# Wifi_RGB_v1.net
KiCad netlist of a schematic drawn in Altium Designer
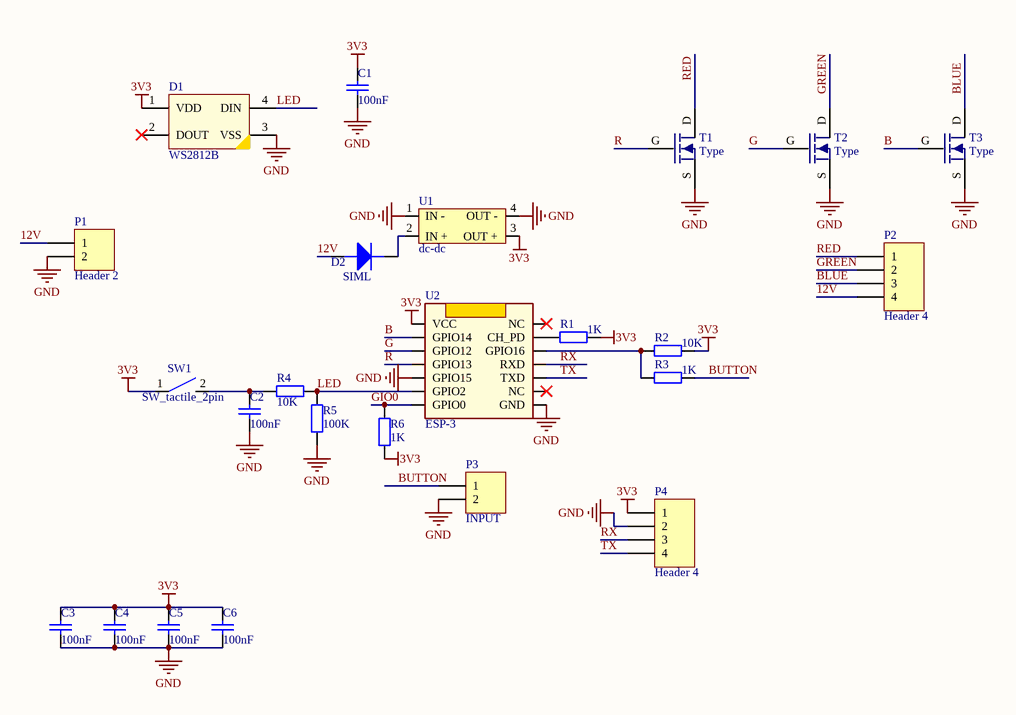
[diagram p0: Wifi_RGB_v1.SchDoc]

(export (version "E")
  (design (tool "Eeschema 10.0.6"))
  (components
    (comp (ref "C1")
      (value "100nF")
      (footprint "FP_0603_CAP_080")
      (description "Capacitor")
      (libsource (lib "Miscellaneous Devices") (part "Cap"))
    )
    (comp (ref "C2")
      (value "100nF")
      (footprint "FP_0603_CAP_080")
      (description "Capacitor")
      (libsource (lib "Miscellaneous Devices") (part "Cap"))
    )
    (comp (ref "C3")
      (value "100nF")
      (footprint "FP_0603_CAP_080")
      (description "Capacitor")
      (libsource (lib "Miscellaneous Devices") (part "Cap"))
    )
    (comp (ref "C4")
      (value "100nF")
      (footprint "FP_0603_CAP_080")
      (description "Capacitor")
      (libsource (lib "Miscellaneous Devices") (part "Cap"))
    )
    (comp (ref "C5")
      (value "100nF")
      (footprint "FP_0603_CAP_080")
      (description "Capacitor")
      (libsource (lib "Miscellaneous Devices") (part "Cap"))
    )
    (comp (ref "C6")
      (value "100nF")
      (footprint "FP_0603_CAP_080")
      (description "Capacitor")
      (libsource (lib "Miscellaneous Devices") (part "Cap"))
    )
    (comp (ref "D1")
      (value "WS2812B")
      (footprint "LED_5050_4pin")
      (libsource (lib "Led_optical") (part "WS2812B"))
    )
    (comp (ref "D2") (value "SIML") (footprint "subsma") (libsource (lib "Diode") (part "DIODE_big")))
    (comp (ref "P1")
      (value "Header 2")
      (footprint "Sorkapocs 2P 5mm")
      (description "Header, 2-Pin")
      (fields (field (name "PUBLISHER") "Altium Limited"))
      (libsource (lib "Miscellaneous Connectors") (part "Header 2"))
    )
    (comp (ref "P2")
      (value "Header 4")
      (footprint "Sorkapocs 4P 5mm")
      (description "Header, 4-Pin")
      (fields (field (name "PUBLISHER") "Altium Limited"))
      (libsource (lib "Miscellaneous Connectors") (part "Header 4"))
    )
    (comp (ref "P3")
      (value "INPUT")
      (footprint "HDR1X2")
      (description "Header, 2-Pin")
      (fields (field (name "PUBLISHER") "Altium Limited"))
      (libsource (lib "Miscellaneous Connectors") (part "Header 2"))
    )
    (comp (ref "P4")
      (value "Header 4")
      (footprint "HDR1X4")
      (description "Header, 4-Pin")
      (fields (field (name "PUBLISHER") "Altium Limited"))
      (libsource (lib "Miscellaneous Connectors") (part "Header 4"))
    )
    (comp (ref "R1")
      (value "1K")
      (footprint "FP_0603_RES")
      (description "Resistor")
      (libsource (lib "Miscellaneous Devices") (part "Res3"))
    )
    (comp (ref "R2")
      (value "10K")
      (footprint "FP_0603_RES")
      (description "Resistor")
      (libsource (lib "Miscellaneous Devices") (part "Res3"))
    )
    (comp (ref "R3")
      (value "1K")
      (footprint "FP_0603_RES")
      (description "Resistor")
      (libsource (lib "Miscellaneous Devices") (part "Res3"))
    )
    (comp (ref "R4")
      (value "10K")
      (footprint "FP_0603_RES")
      (description "Resistor")
      (libsource (lib "") (part "Res3_1"))
    )
    (comp (ref "R5")
      (value "100K")
      (footprint "FP_0603_RES")
      (description "Resistor")
      (libsource (lib "") (part "Res3_2"))
    )
    (comp (ref "R6")
      (value "1K")
      (footprint "FP_0603_RES")
      (description "Resistor")
      (libsource (lib "") (part "Res3_2"))
    )
    (comp (ref "SW1")
      (value "SW_tactile_2pin")
      (footprint "SW_TACT_2PIN")
      (libsource (lib "Switch") (part "SW_tactile_2pin"))
    )
    (comp (ref "T1") (value "Type") (footprint "FET_SOT23") (libsource (lib "FET") (part "NMOS")))
    (comp (ref "T2") (value "Type") (footprint "FET_SOT23") (libsource (lib "FET") (part "NMOS")))
    (comp (ref "T3") (value "Type") (footprint "FET_SOT23") (libsource (lib "FET") (part "NMOS")))
    (comp (ref "U1")
      (value "dc-dc")
      (footprint "DC-DC modul")
      (description "Step down dc-dc module")
      (libsource (lib "Modul") (part "DC-DC modul"))
    )
    (comp (ref "U2")
      (value "ESP-3")
      (footprint "ESP_3")
      (description "ESP-3wifi module")
      (libsource (lib "Modul") (part "ESP-3"))
    )
  )
  (nets
    (net (code "1") (name "/12V") (class "Default")
      (node (ref "D2") (pin "A") (pinfunction "A_A") (pintype "passive"))
      (node (ref "P1") (pin "1") (pinfunction "1_1") (pintype "passive"))
      (node (ref "P2") (pin "4") (pinfunction "4_4") (pintype "passive"))
    )
    (net (code "2") (name "/B") (class "Default")
      (node (ref "T3") (pin "G") (pinfunction "G_G") (pintype "passive"))
      (node (ref "U2") (pin "2") (pinfunction "GPIO14_2") (pintype "passive"))
    )
    (net (code "3") (name "/BLUE") (class "Default")
      (node (ref "P2") (pin "3") (pinfunction "3_3") (pintype "passive"))
      (node (ref "T3") (pin "D") (pinfunction "D_D") (pintype "passive"))
    )
    (net (code "4") (name "/BUTTON") (class "Default")
      (node (ref "P3") (pin "1") (pinfunction "1_1") (pintype "passive"))
      (node (ref "R3") (pin "1") (pinfunction "1_1") (pintype "passive"))
    )
    (net (code "5") (name "/G") (class "Default")
      (node (ref "T2") (pin "G") (pinfunction "G_G") (pintype "passive"))
      (node (ref "U2") (pin "3") (pinfunction "GPIO12_3") (pintype "passive"))
    )
    (net (code "6") (name "/GIO0") (class "Default")
      (node (ref "R6") (pin "1") (pinfunction "1_1") (pintype "passive"))
      (node (ref "U2") (pin "7") (pinfunction "GPIO0_7") (pintype "passive"))
    )
    (net (code "7") (name "/GREEN") (class "Default")
      (node (ref "P2") (pin "2") (pinfunction "2_2") (pintype "passive"))
      (node (ref "T2") (pin "D") (pinfunction "D_D") (pintype "passive"))
    )
    (net (code "8") (name "/LED") (class "Default")
      (node (ref "D1") (pin "4") (pinfunction "DIN_4") (pintype "passive"))
      (node (ref "R4") (pin "2") (pinfunction "2_2") (pintype "passive"))
      (node (ref "R5") (pin "1") (pinfunction "1_1") (pintype "passive"))
      (node (ref "U2") (pin "6") (pinfunction "GPIO2_6") (pintype "passive"))
    )
    (net (code "9") (name "/R") (class "Default")
      (node (ref "T1") (pin "G") (pinfunction "G_G") (pintype "passive"))
      (node (ref "U2") (pin "4") (pinfunction "GPIO13_4") (pintype "passive"))
    )
    (net (code "10") (name "/RED") (class "Default")
      (node (ref "P2") (pin "1") (pinfunction "1_1") (pintype "passive"))
      (node (ref "T1") (pin "D") (pinfunction "D_D") (pintype "passive"))
    )
    (net (code "11") (name "/RX") (class "Default")
      (node (ref "P4") (pin "3") (pinfunction "3_3") (pintype "passive"))
      (node (ref "U2") (pin "11") (pinfunction "RXD_11") (pintype "passive"))
    )
    (net (code "12") (name "/TX") (class "Default")
      (node (ref "P4") (pin "4") (pinfunction "4_4") (pintype "passive"))
      (node (ref "U2") (pin "10") (pinfunction "TXD_10") (pintype "passive"))
    )
    (net (code "13") (name "3V3") (class "Default")
      (node (ref "C1") (pin "1") (pinfunction "1_1") (pintype "passive"))
      (node (ref "C3") (pin "1") (pinfunction "1_1") (pintype "passive"))
      (node (ref "C4") (pin "1") (pinfunction "1_1") (pintype "passive"))
      (node (ref "C5") (pin "1") (pinfunction "1_1") (pintype "passive"))
      (node (ref "C6") (pin "1") (pinfunction "1_1") (pintype "passive"))
      (node (ref "D1") (pin "1") (pinfunction "VDD_1") (pintype "passive"))
      (node (ref "P4") (pin "1") (pinfunction "1_1") (pintype "passive"))
      (node (ref "R1") (pin "1") (pinfunction "1_1") (pintype "passive"))
      (node (ref "R2") (pin "1") (pinfunction "1_1") (pintype "passive"))
      (node (ref "R6") (pin "2") (pinfunction "2_2") (pintype "passive"))
      (node (ref "SW1") (pin "1") (pinfunction "1_1") (pintype "passive"))
      (node (ref "U1") (pin "3") (pinfunction "OUT_+_3") (pintype "passive"))
      (node (ref "U2") (pin "1") (pinfunction "VCC_1") (pintype "passive"))
    )
    (net (code "14") (name "GND") (class "Default")
      (node (ref "C1") (pin "2") (pinfunction "2_2") (pintype "passive"))
      (node (ref "C2") (pin "2") (pinfunction "2_2") (pintype "passive"))
      (node (ref "C3") (pin "2") (pinfunction "2_2") (pintype "passive"))
      (node (ref "C4") (pin "2") (pinfunction "2_2") (pintype "passive"))
      (node (ref "C5") (pin "2") (pinfunction "2_2") (pintype "passive"))
      (node (ref "C6") (pin "2") (pinfunction "2_2") (pintype "passive"))
      (node (ref "D1") (pin "3") (pinfunction "VSS_3") (pintype "passive"))
      (node (ref "P1") (pin "2") (pinfunction "2_2") (pintype "passive"))
      (node (ref "P3") (pin "2") (pinfunction "2_2") (pintype "passive"))
      (node (ref "P4") (pin "2") (pinfunction "2_2") (pintype "passive"))
      (node (ref "R5") (pin "2") (pinfunction "2_2") (pintype "passive"))
      (node (ref "T1") (pin "S") (pinfunction "S_S") (pintype "passive"))
      (node (ref "T2") (pin "S") (pinfunction "S_S") (pintype "passive"))
      (node (ref "T3") (pin "S") (pinfunction "S_S") (pintype "passive"))
      (node (ref "U1") (pin "1") (pinfunction "IN_-_1") (pintype "passive"))
      (node (ref "U1") (pin "4") (pinfunction "OUT_-_4") (pintype "passive"))
      (node (ref "U2") (pin "5") (pinfunction "GPIO15_5") (pintype "passive"))
      (node (ref "U2") (pin "8") (pinfunction "GND_8") (pintype "passive"))
    )
    (net (code "15") (name "Net-(C2-Pad1)") (class "Default")
      (node (ref "C2") (pin "1") (pinfunction "1_1") (pintype "passive"))
      (node (ref "R4") (pin "1") (pinfunction "1_1") (pintype "passive"))
      (node (ref "SW1") (pin "2") (pinfunction "2_2") (pintype "passive"))
    )
    (net (code "16") (name "Net-(U1-IN_+)") (class "Default")
      (node (ref "D2") (pin "K") (pinfunction "K_K") (pintype "passive"))
      (node (ref "U1") (pin "2") (pinfunction "IN_+_2") (pintype "passive"))
    )
    (net (code "17") (name "Net-(U2-CH_PD)") (class "Default")
      (node (ref "R1") (pin "2") (pinfunction "2_2") (pintype "passive"))
      (node (ref "U2") (pin "13") (pinfunction "CH_PD_13") (pintype "passive"))
    )
    (net (code "18") (name "Net-(U2-GPIO16)") (class "Default")
      (node (ref "R2") (pin "2") (pinfunction "2_2") (pintype "passive"))
      (node (ref "R3") (pin "2") (pinfunction "2_2") (pintype "passive"))
      (node (ref "U2") (pin "12") (pinfunction "GPIO16_12") (pintype "passive"))
    )
    (net (code "19") (name "unconnected-(D1-DOUT-Pad2)") (class "Default")
      (node (ref "D1") (pin "2") (pinfunction "DOUT_2") (pintype "passive+no_connect"))
    )
    (net (code "20") (name "unconnected-(U2-NC-Pad9)") (class "Default")
      (node (ref "U2") (pin "9") (pinfunction "NC_9") (pintype "passive+no_connect"))
    )
    (net (code "21") (name "unconnected-(U2-NC-Pad14)") (class "Default")
      (node (ref "U2") (pin "14") (pinfunction "NC_14") (pintype "passive+no_connect"))
    )
  )
)
